# 05io.net
KiCad netlist of a schematic drawn in Altium Designer
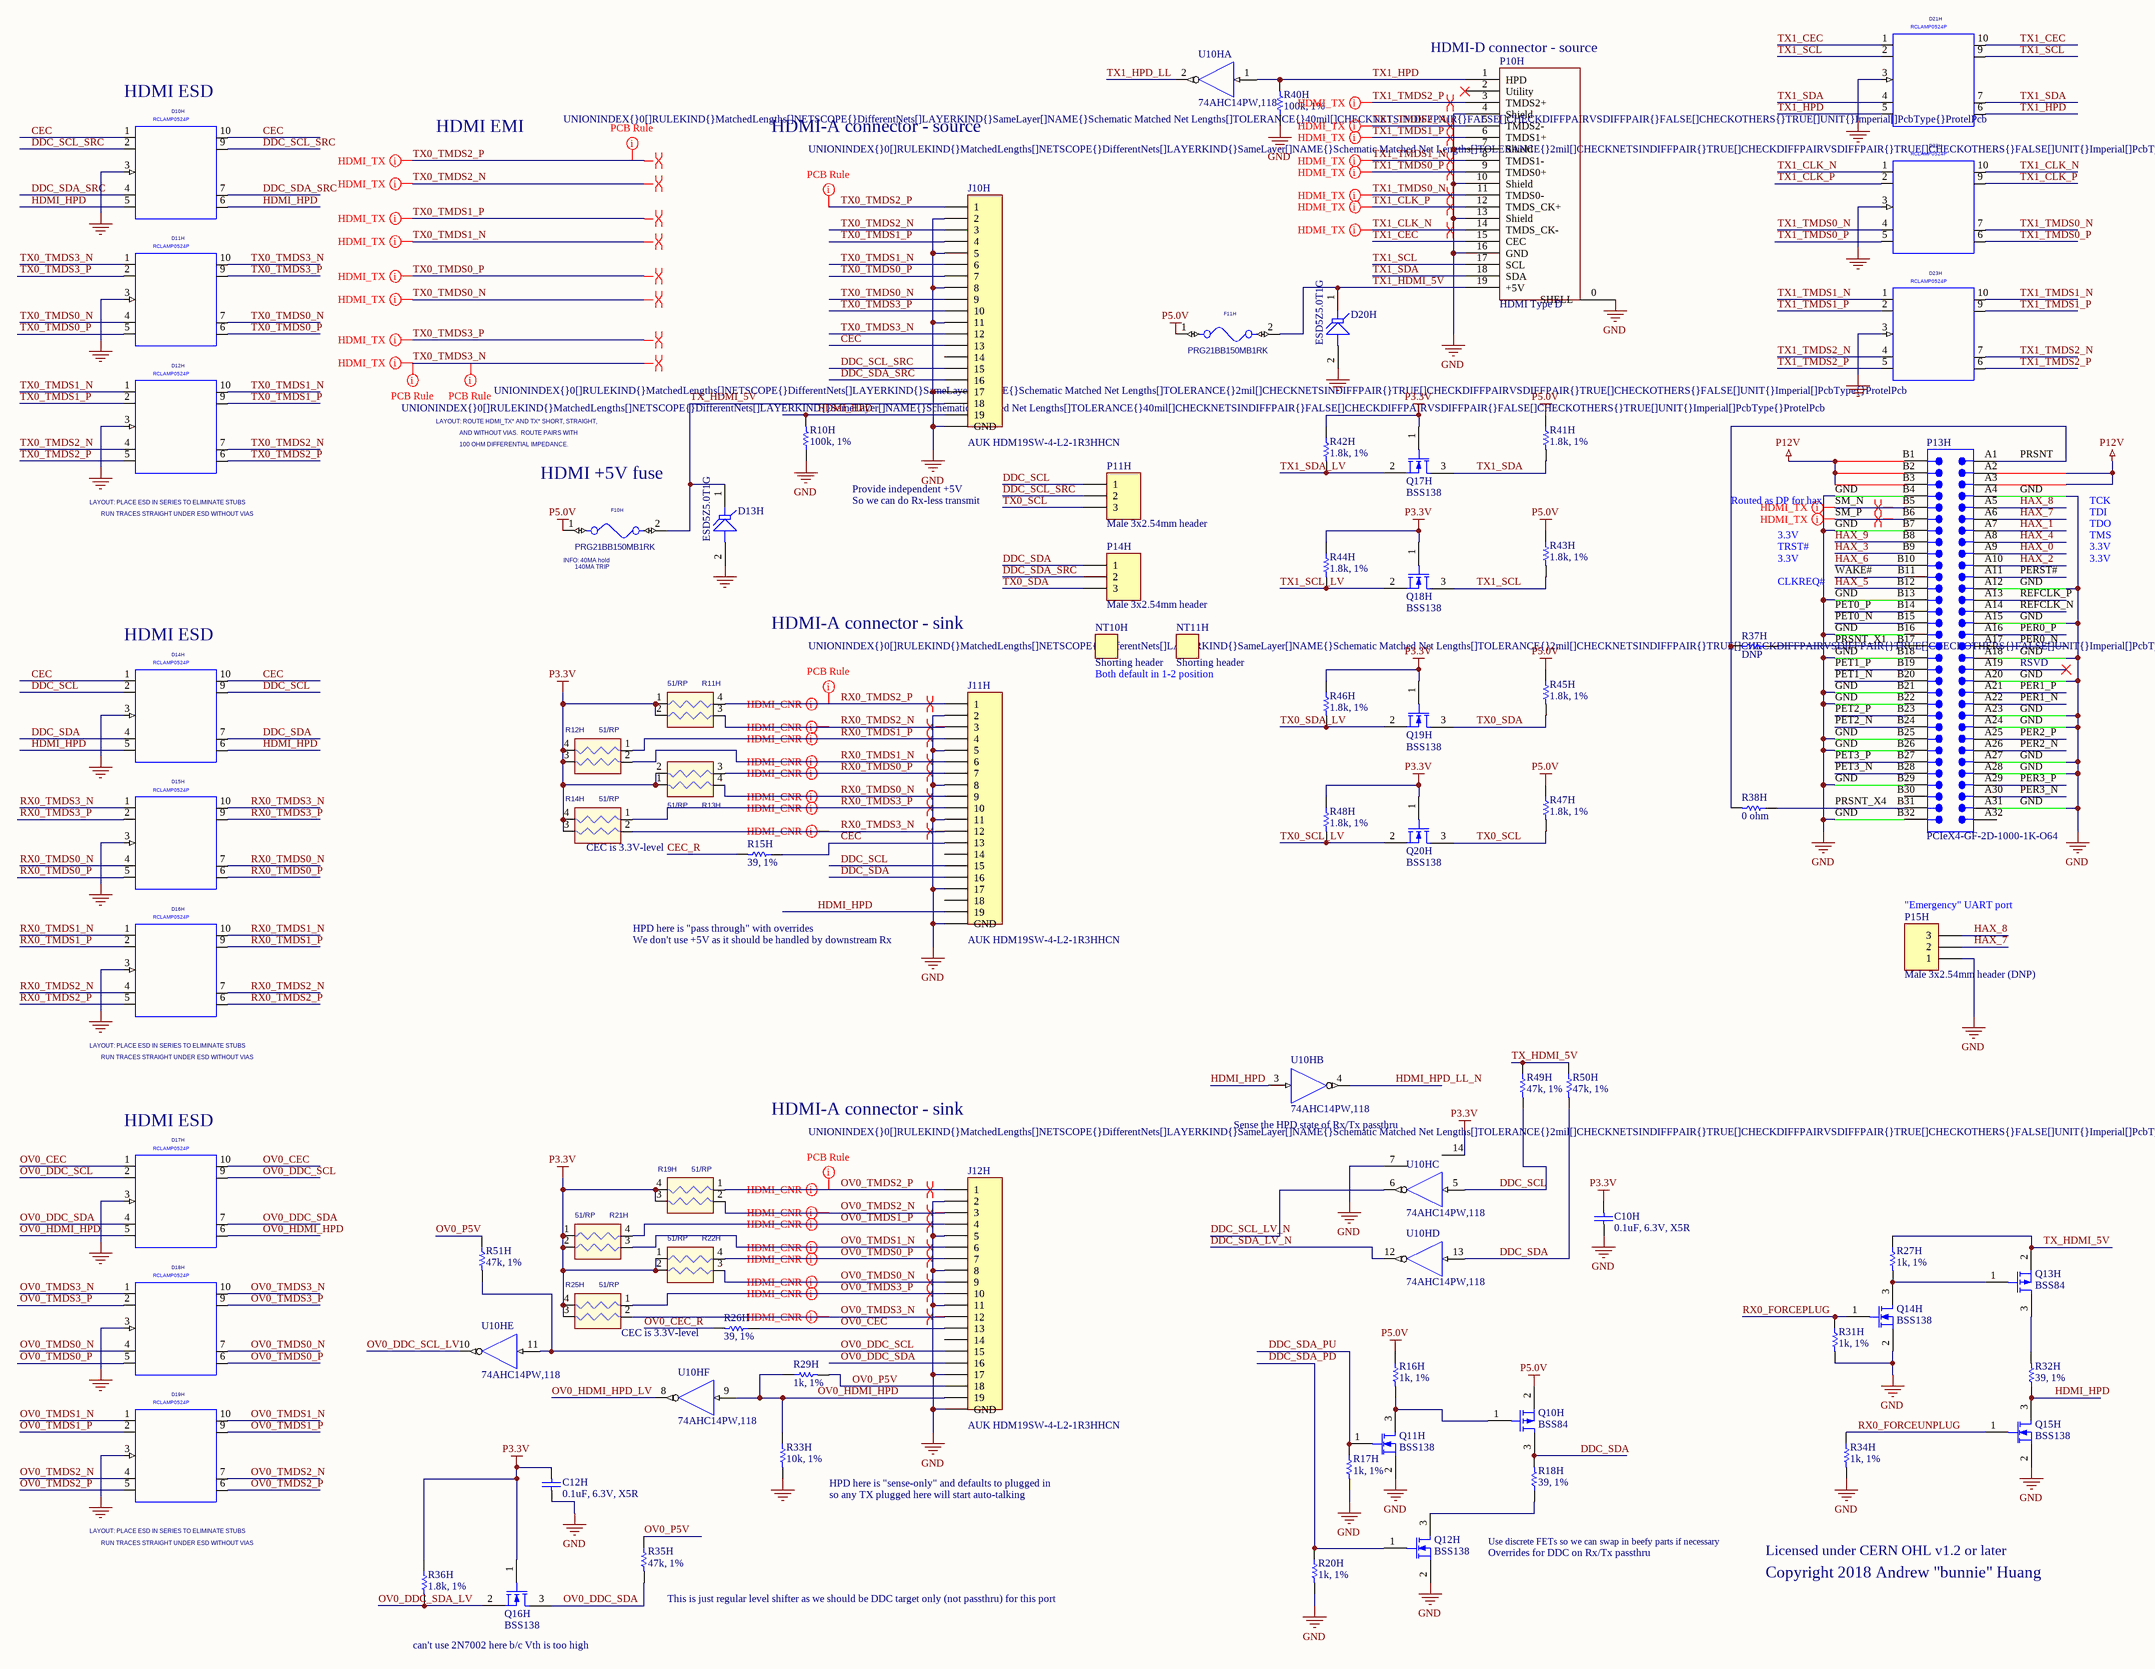
[diagram p0: 05io.SchDoc]

(export (version "E")
  (design (tool "Eeschema 10.0.6"))
  (components
    (comp (ref "C10H")
      (value "0.1uF, 6.3V, X5R")
      (footprint "CAPC0603X03L")
      (description "Capacitor (Semiconductor SIM Model)")
      (fields (field (name "MPN") "CL03A104KQ3NNNC"))
      (libsource (lib "Miscellaneous Devices") (part "Cap Semi"))
    )
    (comp (ref "C12H")
      (value "0.1uF, 6.3V, X5R")
      (footprint "CAPC0603X03L")
      (description "Capacitor (Semiconductor SIM Model)")
      (fields (field (name "MPN") "CL03A104KQ3NNNC"))
      (libsource (lib "Miscellaneous Devices") (part "Cap Semi"))
    )
    (comp (ref "D10H")
      (value "RCLAMP0524P")
      (fields (field (name "PART_NUMBER") "V00004-001") (field (name "MPN") "RCLAMP0524PATCT"))
      (libsource (lib "*") (part "RCLAMP0524P"))
    )
    (comp (ref "D11H")
      (value "RCLAMP0524P")
      (fields (field (name "PART_NUMBER") "V00004-001") (field (name "MPN") "RCLAMP0524PATCT"))
      (libsource (lib "*") (part "RCLAMP0524P"))
    )
    (comp (ref "D12H")
      (value "RCLAMP0524P")
      (fields (field (name "PART_NUMBER") "V00004-001") (field (name "MPN") "RCLAMP0524PATCT"))
      (libsource (lib "*") (part "RCLAMP0524P"))
    )
    (comp (ref "D13H")
      (value "ESD5Z5.0T1G")
      (footprint "SOD-523")
      (description "On Semi 5.0V standoff TVS diode")
      (fields (field (name "PUBLISHER") "Altium Limited"))
      (libsource (lib "Miscellaneous Devices") (part "Tranzorb"))
    )
    (comp (ref "D14H")
      (value "RCLAMP0524P")
      (fields (field (name "PART_NUMBER") "V00004-001") (field (name "MPN") "RCLAMP0524PATCT"))
      (libsource (lib "*") (part "RCLAMP0524P"))
    )
    (comp (ref "D15H")
      (value "RCLAMP0524P")
      (fields (field (name "PART_NUMBER") "V00004-001") (field (name "MPN") "RCLAMP0524PATCT"))
      (libsource (lib "*") (part "RCLAMP0524P"))
    )
    (comp (ref "D16H")
      (value "RCLAMP0524P")
      (fields (field (name "PART_NUMBER") "V00004-001") (field (name "MPN") "RCLAMP0524PATCT"))
      (libsource (lib "*") (part "RCLAMP0524P"))
    )
    (comp (ref "D17H")
      (value "RCLAMP0524P")
      (fields (field (name "PART_NUMBER") "V00004-001") (field (name "MPN") "RCLAMP0524PATCT"))
      (libsource (lib "*") (part "RCLAMP0524P"))
    )
    (comp (ref "D18H")
      (value "RCLAMP0524P")
      (fields (field (name "PART_NUMBER") "V00004-001") (field (name "MPN") "RCLAMP0524PATCT"))
      (libsource (lib "*") (part "RCLAMP0524P"))
    )
    (comp (ref "D19H")
      (value "RCLAMP0524P")
      (fields (field (name "PART_NUMBER") "V00004-001") (field (name "MPN") "RCLAMP0524PATCT"))
      (libsource (lib "*") (part "RCLAMP0524P"))
    )
    (comp (ref "D20H")
      (value "ESD5Z5.0T1G")
      (footprint "SOD-523")
      (description "On Semi 5.0V standoff TVS diode")
      (fields (field (name "PUBLISHER") "Altium Limited"))
      (libsource (lib "Miscellaneous Devices") (part "Tranzorb"))
    )
    (comp (ref "D21H")
      (value "RCLAMP0524P")
      (fields (field (name "PART_NUMBER") "V00004-001") (field (name "MPN") "RCLAMP0524PATCT"))
      (libsource (lib "*") (part "RCLAMP0524P"))
    )
    (comp (ref "D22H")
      (value "RCLAMP0524P")
      (fields (field (name "PART_NUMBER") "V00004-001") (field (name "MPN") "RCLAMP0524PATCT"))
      (libsource (lib "*") (part "RCLAMP0524P"))
    )
    (comp (ref "D23H")
      (value "RCLAMP0524P")
      (fields (field (name "PART_NUMBER") "V00004-001") (field (name "MPN") "RCLAMP0524PATCT"))
      (libsource (lib "*") (part "RCLAMP0524P"))
    )
    (comp (ref "F10H")
      (value "PRG21BB150MB1RK")
      (description "Murata 140mA fuse, 40mA hold")
      (fields (field (name "PART_NUMBER") "M00014-001") (field (name "MPN") "0ZCK0010FF2G"))
      (libsource (lib "*") (part "FUSE0805"))
    )
    (comp (ref "F11H")
      (value "PRG21BB150MB1RK")
      (description "Murata 140mA fuse, 40mA hold")
      (fields (field (name "PART_NUMBER") "M00014-001") (field (name "MPN") "0ZCK0010FF2G"))
      (libsource (lib "*") (part "FUSE0805"))
    )
    (comp (ref "J10H")
      (value "AUK HDM19SW-4-L2-1R3HHCN")
      (footprint "MOLEX_47151-0001")
      (description "Molex HDMI connector, Type A")
      (fields (field (name "MPN") "CHDMI-AFM2S-01-D") (field (name "PUBLISHER") "Altium Limited"))
      (libsource (lib "Miscellaneous Connectors") (part "Header 19"))
    )
    (comp (ref "J11H")
      (value "AUK HDM19SW-4-L2-1R3HHCN")
      (footprint "MOLEX_47151-0001")
      (description "Molex HDMI connector, Type A")
      (fields (field (name "MPN") "CHDMI-AFM2S-01-D") (field (name "PUBLISHER") "Altium Limited"))
      (libsource (lib "Miscellaneous Connectors") (part "Header 19"))
    )
    (comp (ref "J12H")
      (value "AUK HDM19SW-4-L2-1R3HHCN")
      (footprint "MOLEX_47151-0001")
      (description "Molex HDMI connector, Type A")
      (fields (field (name "MPN") "CHDMI-AFM2S-01-D") (field (name "PUBLISHER") "Altium Limited"))
      (libsource (lib "Miscellaneous Connectors") (part "Header 19"))
    )
    (comp (ref "NT10H")
      (value "Shorting header")
      (description "Placeholder for non-board BOM items")
      (fields (field (name "MPN") "NPB02SVAN-RC"))
      (libsource (lib "commonsch") (part "NOTE"))
    )
    (comp (ref "NT11H")
      (value "Shorting header")
      (description "Placeholder for non-board BOM items")
      (fields (field (name "MPN") "NPB02SVAN-RC"))
      (libsource (lib "commonsch") (part "NOTE"))
    )
    (comp (ref "P10H")
      (value "HDMI Type D")
      (footprint "MOLEX_0467651301")
      (description "HDMI Type D with through-hole mounts")
      (fields (field (name "MPN") "CHDMI-DFMS-01-D"))
      (libsource (lib "commonsch-new") (part "HDMI-TYPE-D"))
    )
    (comp (ref "P11H")
      (value "Male 3x2.54mm header")
      (footprint "HDR1X3")
      (description "Header, 3-Pin")
      (fields (field (name "MPN") "CP25411-03G-S116-X") (field (name "PUBLISHER") "Altium Limited"))
      (libsource (lib "Miscellaneous Connectors") (part "Header 3"))
    )
    (comp (ref "P13H")
      (value "PCIeX4-GF-2D-1000-1K-O64")
      (footprint "PCIeX4-GF-2D-1000-1K-O64")
      (description "Golden finger, PCIeX4, Dual, Opposite, Pitch 1mm, 64-Position")
      (fields (field (name "PUBLISHER") "Altium"))
      (libsource (lib "altium-import") (part "root_3_CMP-0001-00031-1_"))
    )
    (comp (ref "P14H")
      (value "Male 3x2.54mm header")
      (footprint "HDR1X3")
      (description "Header, 3-Pin")
      (fields (field (name "MPN") "CP25411-03G-S116-X") (field (name "PUBLISHER") "Altium Limited"))
      (libsource (lib "Miscellaneous Connectors") (part "Header 3"))
    )
    (comp (ref "P15H")
      (value "Male 3x2.54mm header (DNP)")
      (footprint "HDR1X3")
      (description "Header, 3-Pin")
      (fields (field (name "MPN") "DNP") (field (name "PUBLISHER") "Altium Limited"))
      (libsource (lib "") (part "Header 3_1"))
    )
    (comp (ref "Q10H")
      (value "BSS84")
      (footprint "SOT23-3N")
      (description "P-Channel MOSFET")
      (fields (field (name "PUBLISHER") "Altium Limited"))
      (libsource (lib "Miscellaneous Devices") (part "MOSFET-P"))
    )
    (comp (ref "Q11H")
      (value "BSS138")
      (footprint "SOT23-3N")
      (description "N-Channel MOSFET")
      (fields (field (name "MPN") "BSS138LT1G") (field (name "PUBLISHER") "Altium Limited"))
      (libsource (lib "Miscellaneous Devices") (part "MOSFET-N"))
    )
    (comp (ref "Q12H")
      (value "BSS138")
      (footprint "SOT23-3N")
      (description "N-Channel MOSFET")
      (fields (field (name "MPN") "BSS138LT1G") (field (name "PUBLISHER") "Altium Limited"))
      (libsource (lib "Miscellaneous Devices") (part "MOSFET-N"))
    )
    (comp (ref "Q13H")
      (value "BSS84")
      (footprint "SOT23-3N")
      (description "P-Channel MOSFET")
      (fields (field (name "PUBLISHER") "Altium Limited"))
      (libsource (lib "Miscellaneous Devices") (part "MOSFET-P"))
    )
    (comp (ref "Q14H")
      (value "BSS138")
      (footprint "SOT23-3N")
      (description "N-Channel MOSFET")
      (fields (field (name "MPN") "BSS138LT1G") (field (name "PUBLISHER") "Altium Limited"))
      (libsource (lib "Miscellaneous Devices") (part "MOSFET-N"))
    )
    (comp (ref "Q15H")
      (value "BSS138")
      (footprint "SOT23-3N")
      (description "N-Channel MOSFET")
      (fields (field (name "MPN") "BSS138LT1G") (field (name "PUBLISHER") "Altium Limited"))
      (libsource (lib "Miscellaneous Devices") (part "MOSFET-N"))
    )
    (comp (ref "Q16H")
      (value "BSS138")
      (footprint "SOT23-3N")
      (description "N-Channel MOSFET")
      (fields (field (name "MPN") "BSS138LT1G") (field (name "PUBLISHER") "Altium Limited"))
      (libsource (lib "Miscellaneous Devices") (part "MOSFET-N"))
    )
    (comp (ref "Q17H")
      (value "BSS138")
      (footprint "SOT23-3N")
      (description "N-Channel MOSFET")
      (fields (field (name "MPN") "BSS138LT1G") (field (name "PUBLISHER") "Altium Limited"))
      (libsource (lib "Miscellaneous Devices") (part "MOSFET-N"))
    )
    (comp (ref "Q18H")
      (value "BSS138")
      (footprint "SOT23-3N")
      (description "N-Channel MOSFET")
      (fields (field (name "MPN") "BSS138LT1G") (field (name "PUBLISHER") "Altium Limited"))
      (libsource (lib "Miscellaneous Devices") (part "MOSFET-N"))
    )
    (comp (ref "Q19H")
      (value "BSS138")
      (footprint "SOT23-3N")
      (description "N-Channel MOSFET")
      (fields (field (name "MPN") "BSS138LT1G") (field (name "PUBLISHER") "Altium Limited"))
      (libsource (lib "Miscellaneous Devices") (part "MOSFET-N"))
    )
    (comp (ref "Q20H")
      (value "BSS138")
      (footprint "SOT23-3N")
      (description "N-Channel MOSFET")
      (fields (field (name "MPN") "BSS138LT1G") (field (name "PUBLISHER") "Altium Limited"))
      (libsource (lib "Miscellaneous Devices") (part "MOSFET-N"))
    )
    (comp (ref "R10H")
      (value "100k, 1%")
      (footprint "RESC1005N")
      (description "Resistor")
      (fields (field (name "MPN") "ANY"))
      (libsource (lib "Miscellaneous Devices") (part "Res1"))
    )
    (comp (ref "R11H")
      (value "51/RP")
      (fields (field (name "MPN") "RP102PJ510CS") (field (name "MFG") "SAMSUNG"))
      (libsource (lib "*") (part "RPACK2"))
    )
    (comp (ref "R12H")
      (value "51/RP")
      (fields (field (name "MPN") "RP102PJ510CS") (field (name "MFG") "SAMSUNG"))
      (libsource (lib "") (part "RPACK2_1"))
    )
    (comp (ref "R13H")
      (value "51/RP")
      (fields (field (name "MPN") "RP102PJ510CS") (field (name "MFG") "SAMSUNG"))
      (libsource (lib "") (part "RPACK2_2"))
    )
    (comp (ref "R14H")
      (value "51/RP")
      (fields (field (name "MPN") "RP102PJ510CS") (field (name "MFG") "SAMSUNG"))
      (libsource (lib "") (part "RPACK2_1"))
    )
    (comp (ref "R15H")
      (value "39, 1%")
      (footprint "RESC1005N")
      (description "Resistor")
      (fields (field (name "MPN") "ANY"))
      (libsource (lib "Miscellaneous Devices") (part "Res1"))
    )
    (comp (ref "R16H")
      (value "1k, 1%")
      (footprint "RESC1005N")
      (description "Resistor")
      (fields (field (name "MPN") "RS02U102FT"))
      (libsource (lib "Miscellaneous Devices") (part "Res1"))
    )
    (comp (ref "R17H")
      (value "1k, 1%")
      (footprint "RESC1005N")
      (description "Resistor")
      (fields (field (name "MPN") "RS02U102FT"))
      (libsource (lib "Miscellaneous Devices") (part "Res1"))
    )
    (comp (ref "R18H")
      (value "39, 1%")
      (footprint "RESC1005N")
      (description "Resistor")
      (fields (field (name "MPN") "ANY"))
      (libsource (lib "Miscellaneous Devices") (part "Res1"))
    )
    (comp (ref "R19H")
      (value "51/RP")
      (fields (field (name "MPN") "RP102PJ510CS") (field (name "MFG") "SAMSUNG"))
      (libsource (lib "") (part "RPACK2_1"))
    )
    (comp (ref "R20H")
      (value "1k, 1%")
      (footprint "RESC1005N")
      (description "Resistor")
      (fields (field (name "MPN") "RS02U102FT"))
      (libsource (lib "Miscellaneous Devices") (part "Res1"))
    )
    (comp (ref "R21H")
      (value "51/RP")
      (fields (field (name "MPN") "RP102PJ510CS") (field (name "MFG") "SAMSUNG"))
      (libsource (lib "*") (part "RPACK2"))
    )
    (comp (ref "R22H")
      (value "51/RP")
      (fields (field (name "MPN") "RP102PJ510CS") (field (name "MFG") "SAMSUNG"))
      (libsource (lib "*") (part "RPACK2"))
    )
    (comp (ref "R25H")
      (value "51/RP")
      (fields (field (name "MPN") "RP102PJ510CS") (field (name "MFG") "SAMSUNG"))
      (libsource (lib "") (part "RPACK2_1"))
    )
    (comp (ref "R26H")
      (value "39, 1%")
      (footprint "RESC1005N")
      (description "Resistor")
      (fields (field (name "MPN") "ANY"))
      (libsource (lib "Miscellaneous Devices") (part "Res1"))
    )
    (comp (ref "R27H")
      (value "1k, 1%")
      (footprint "RESC1005N")
      (description "Resistor")
      (fields (field (name "MPN") "RS02U102FT"))
      (libsource (lib "Miscellaneous Devices") (part "Res1"))
    )
    (comp (ref "R29H")
      (value "1k, 1%")
      (footprint "RESC1005N")
      (description "Resistor")
      (fields (field (name "MPN") "RS02U102FT"))
      (libsource (lib "Miscellaneous Devices") (part "Res1"))
    )
    (comp (ref "R31H")
      (value "1k, 1%")
      (footprint "RESC1005N")
      (description "Resistor")
      (fields (field (name "MPN") "RS02U102FT"))
      (libsource (lib "Miscellaneous Devices") (part "Res1"))
    )
    (comp (ref "R32H")
      (value "39, 1%")
      (footprint "RESC1005N")
      (description "Resistor")
      (fields (field (name "MPN") "ANY"))
      (libsource (lib "Miscellaneous Devices") (part "Res1"))
    )
    (comp (ref "R33H")
      (value "10k, 1%")
      (footprint "RESC1005N")
      (description "Resistor")
      (fields (field (name "MPN") "RS02U103FT"))
      (libsource (lib "Miscellaneous Devices") (part "Res1"))
    )
    (comp (ref "R34H")
      (value "1k, 1%")
      (footprint "RESC1005N")
      (description "Resistor")
      (fields (field (name "MPN") "RS02U102FT"))
      (libsource (lib "Miscellaneous Devices") (part "Res1"))
    )
    (comp (ref "R35H")
      (value "47k, 1%")
      (footprint "RESC1005N")
      (description "Resistor")
      (fields (field (name "MPN") "RS02U473FT") (field (name "PUBLISHER") "Altium Limited"))
      (libsource (lib "Miscellaneous Devices") (part "Res1"))
    )
    (comp (ref "R36H")
      (value "1.8k, 1%")
      (footprint "RESC1005N")
      (description "Resistor")
      (fields (field (name "MPN") "RS02U182FT") (field (name "PUBLISHER") "Altium Limited"))
      (libsource (lib "Miscellaneous Devices") (part "Res1"))
    )
    (comp (ref "R37H")
      (value "DNP")
      (footprint "RESC1608N")
      (description "Resistor")
      (fields (field (name "MPN") "ANY"))
      (libsource (lib "Miscellaneous Devices") (part "Res1"))
    )
    (comp (ref "R38H")
      (value "0 ohm")
      (footprint "RESC1608N")
      (description "Resistor")
      (fields (field (name "MPN") "ANY"))
      (libsource (lib "Miscellaneous Devices") (part "Res1"))
    )
    (comp (ref "R40H")
      (value "100k, 1%")
      (footprint "RESC1005N")
      (description "Resistor")
      (fields (field (name "MPN") "ANY"))
      (libsource (lib "Miscellaneous Devices") (part "Res1"))
    )
    (comp (ref "R41H")
      (value "1.8k, 1%")
      (footprint "RESC1005N")
      (description "Resistor")
      (fields (field (name "MPN") "RS02U182FT") (field (name "PUBLISHER") "Altium Limited"))
      (libsource (lib "Miscellaneous Devices") (part "Res1"))
    )
    (comp (ref "R42H")
      (value "1.8k, 1%")
      (footprint "RESC1005N")
      (description "Resistor")
      (fields (field (name "MPN") "RS02U182FT") (field (name "PUBLISHER") "Altium Limited"))
      (libsource (lib "Miscellaneous Devices") (part "Res1"))
    )
    (comp (ref "R43H")
      (value "1.8k, 1%")
      (footprint "RESC1005N")
      (description "Resistor")
      (fields (field (name "MPN") "RS02U182FT") (field (name "PUBLISHER") "Altium Limited"))
      (libsource (lib "Miscellaneous Devices") (part "Res1"))
    )
    (comp (ref "R44H")
      (value "1.8k, 1%")
      (footprint "RESC1005N")
      (description "Resistor")
      (fields (field (name "MPN") "RS02U182FT") (field (name "PUBLISHER") "Altium Limited"))
      (libsource (lib "Miscellaneous Devices") (part "Res1"))
    )
    (comp (ref "R45H")
      (value "1.8k, 1%")
      (footprint "RESC1005N")
      (description "Resistor")
      (fields (field (name "MPN") "RS02U182FT") (field (name "PUBLISHER") "Altium Limited"))
      (libsource (lib "Miscellaneous Devices") (part "Res1"))
    )
    (comp (ref "R46H")
      (value "1.8k, 1%")
      (footprint "RESC1005N")
      (description "Resistor")
      (fields (field (name "MPN") "RS02U182FT") (field (name "PUBLISHER") "Altium Limited"))
      (libsource (lib "Miscellaneous Devices") (part "Res1"))
    )
    (comp (ref "R47H")
      (value "1.8k, 1%")
      (footprint "RESC1005N")
      (description "Resistor")
      (fields (field (name "MPN") "RS02U182FT") (field (name "PUBLISHER") "Altium Limited"))
      (libsource (lib "Miscellaneous Devices") (part "Res1"))
    )
    (comp (ref "R48H")
      (value "1.8k, 1%")
      (footprint "RESC1005N")
      (description "Resistor")
      (fields (field (name "MPN") "RS02U182FT") (field (name "PUBLISHER") "Altium Limited"))
      (libsource (lib "Miscellaneous Devices") (part "Res1"))
    )
    (comp (ref "R49H")
      (value "47k, 1%")
      (footprint "RESC1005N")
      (description "Resistor")
      (fields (field (name "MPN") "RS02U473FT") (field (name "PUBLISHER") "Altium Limited"))
      (libsource (lib "Miscellaneous Devices") (part "Res1"))
    )
    (comp (ref "R50H")
      (value "47k, 1%")
      (footprint "RESC1005N")
      (description "Resistor")
      (fields (field (name "MPN") "RS02U473FT") (field (name "PUBLISHER") "Altium Limited"))
      (libsource (lib "Miscellaneous Devices") (part "Res1"))
    )
    (comp (ref "R51H")
      (value "47k, 1%")
      (footprint "RESC1005N")
      (description "Resistor")
      (fields (field (name "MPN") "RS02U473FT") (field (name "PUBLISHER") "Altium Limited"))
      (libsource (lib "Miscellaneous Devices") (part "Res1"))
    )
    (comp (ref "U10H")
      (value "74AHC14PW,118")
      (footprint "TSOP65P640-14AN")
      (description "Hex Inverter, 14-Pin SOIC, Commercial Grade")
      (fields (field (name "PUBLISHER") "Altium Limited"))
      (libsource (lib "FSC Logic Gate") (part "74AC04SC"))
    )
  )
  (nets
    (net (code "1") (name "/CEC") (class "Default")
      (node (ref "D10H") (pin "1") (pinfunction "IO1A_1") (pintype "bidirectional"))
      (node (ref "D10H") (pin "10") (pinfunction "IO1B_10") (pintype "bidirectional"))
      (node (ref "D14H") (pin "1") (pinfunction "IO1A_1") (pintype "bidirectional"))
      (node (ref "D14H") (pin "10") (pinfunction "IO1B_10") (pintype "bidirectional"))
      (node (ref "J10H") (pin "13") (pinfunction "13_13") (pintype "passive"))
      (node (ref "J11H") (pin "13") (pinfunction "13_13") (pintype "passive"))
      (node (ref "R15H") (pin "1") (pinfunction "1_1") (pintype "passive"))
    )
    (net (code "2") (name "/CEC_R") (class "Default")
      (node (ref "R15H") (pin "2") (pinfunction "2_2") (pintype "passive"))
    )
    (net (code "3") (name "/DDC_SCL") (class "Default")
      (node (ref "D14H") (pin "2") (pinfunction "IO2A_2") (pintype "bidirectional"))
      (node (ref "D14H") (pin "9") (pinfunction "IO2B_9") (pintype "bidirectional"))
      (node (ref "J11H") (pin "15") (pinfunction "15_15") (pintype "passive"))
      (node (ref "P11H") (pin "1") (pinfunction "1_1") (pintype "passive"))
      (node (ref "R49H") (pin "2") (pinfunction "2_2") (pintype "passive"))
      (node (ref "U10H") (pin "5") (pinfunction "A_5") (pintype "input"))
    )
    (net (code "4") (name "/DDC_SCL_LV_N") (class "Default")
      (node (ref "U10H") (pin "6") (pinfunction "~{O}_6") (pintype "output"))
    )
    (net (code "5") (name "/DDC_SCL_SRC") (class "Default")
      (node (ref "D10H") (pin "2") (pinfunction "IO2A_2") (pintype "bidirectional"))
      (node (ref "D10H") (pin "9") (pinfunction "IO2B_9") (pintype "bidirectional"))
      (node (ref "J10H") (pin "15") (pinfunction "15_15") (pintype "passive"))
      (node (ref "P11H") (pin "2") (pinfunction "2_2") (pintype "passive"))
    )
    (net (code "6") (name "/DDC_SDA") (class "Default")
      (node (ref "D14H") (pin "4") (pinfunction "IO3A_4") (pintype "bidirectional"))
      (node (ref "D14H") (pin "7") (pinfunction "IO3B_7") (pintype "bidirectional"))
      (node (ref "J11H") (pin "16") (pinfunction "16_16") (pintype "passive"))
      (node (ref "P14H") (pin "1") (pinfunction "1_1") (pintype "passive"))
      (node (ref "Q10H") (pin "3") (pinfunction "D_3") (pintype "passive"))
      (node (ref "R18H") (pin "2") (pinfunction "2_2") (pintype "passive"))
      (node (ref "R50H") (pin "2") (pinfunction "2_2") (pintype "passive"))
      (node (ref "U10H") (pin "13") (pinfunction "A_13") (pintype "input"))
    )
    (net (code "7") (name "/DDC_SDA_LV_N") (class "Default")
      (node (ref "U10H") (pin "12") (pinfunction "~{O}_12") (pintype "output"))
    )
    (net (code "8") (name "/DDC_SDA_PD") (class "Default")
      (node (ref "Q12H") (pin "1") (pinfunction "G_1") (pintype "passive"))
      (node (ref "R20H") (pin "1") (pinfunction "1_1") (pintype "passive"))
    )
    (net (code "9") (name "/DDC_SDA_PU") (class "Default")
      (node (ref "Q11H") (pin "1") (pinfunction "G_1") (pintype "passive"))
      (node (ref "R17H") (pin "1") (pinfunction "1_1") (pintype "passive"))
    )
    (net (code "10") (name "/DDC_SDA_SRC") (class "Default")
      (node (ref "D10H") (pin "4") (pinfunction "IO3A_4") (pintype "bidirectional"))
      (node (ref "D10H") (pin "7") (pinfunction "IO3B_7") (pintype "bidirectional"))
      (node (ref "J10H") (pin "16") (pinfunction "16_16") (pintype "passive"))
      (node (ref "P14H") (pin "2") (pinfunction "2_2") (pintype "passive"))
    )
    (net (code "11") (name "/HAX_0") (class "Default")
      (node (ref "P13H") (pin "A9") (pinfunction "A9_A9") (pintype "passive"))
    )
    (net (code "12") (name "/HAX_1") (class "Default")
      (node (ref "P13H") (pin "A7") (pinfunction "A7_A7") (pintype "passive"))
    )
    (net (code "13") (name "/HAX_2") (class "Default")
      (node (ref "P13H") (pin "A10") (pinfunction "A10_A10") (pintype "passive"))
    )
    (net (code "14") (name "/HAX_3") (class "Default")
      (node (ref "P13H") (pin "B9") (pinfunction "B9_B9") (pintype "passive"))
    )
    (net (code "15") (name "/HAX_4") (class "Default")
      (node (ref "P13H") (pin "A8") (pinfunction "A8_A8") (pintype "passive"))
    )
    (net (code "16") (name "/HAX_5") (class "Default")
      (node (ref "P13H") (pin "B12") (pinfunction "B12_B12") (pintype "passive"))
    )
    (net (code "17") (name "/HAX_6") (class "Default")
      (node (ref "P13H") (pin "B10") (pinfunction "B10_B10") (pintype "passive"))
    )
    (net (code "18") (name "/HAX_7") (class "Default")
      (node (ref "P13H") (pin "A6") (pinfunction "A6_A6") (pintype "passive"))
      (node (ref "P15H") (pin "2") (pinfunction "2_2") (pintype "passive"))
    )
    (net (code "19") (name "/HAX_8") (class "Default")
      (node (ref "P13H") (pin "A5") (pinfunction "A5_A5") (pintype "passive"))
      (node (ref "P15H") (pin "3") (pinfunction "3_3") (pintype "passive"))
    )
    (net (code "20") (name "/HAX_9") (class "Default")
      (node (ref "P13H") (pin "B8") (pinfunction "B8_B8") (pintype "passive"))
    )
    (net (code "21") (name "/HDMI_HPD") (class "Default")
      (node (ref "D10H") (pin "5") (pinfunction "IO4A_5") (pintype "bidirectional"))
      (node (ref "D10H") (pin "6") (pinfunction "IO4B_6") (pintype "bidirectional"))
      (node (ref "D14H") (pin "5") (pinfunction "IO4A_5") (pintype "bidirectional"))
      (node (ref "D14H") (pin "6") (pinfunction "IO4B_6") (pintype "bidirectional"))
      (node (ref "J10H") (pin "19") (pinfunction "19_19") (pintype "passive"))
      (node (ref "J11H") (pin "19") (pinfunction "19_19") (pintype "passive"))
      (node (ref "Q15H") (pin "3") (pinfunction "D_3") (pintype "passive"))
      (node (ref "R10H") (pin "2") (pinfunction "2_2") (pintype "passive"))
      (node (ref "R32H") (pin "1") (pinfunction "1_1") (pintype "passive"))
      (node (ref "U10H") (pin "3") (pinfunction "A_3") (pintype "input"))
    )
    (net (code "22") (name "/HDMI_HPD_LL_N") (class "Default")
      (node (ref "U10H") (pin "4") (pinfunction "~{O}_4") (pintype "output"))
    )
    (net (code "23") (name "/OV0_CEC") (class "Default")
      (node (ref "D17H") (pin "1") (pinfunction "IO1A_1") (pintype "bidirectional"))
      (node (ref "D17H") (pin "10") (pinfunction "IO1B_10") (pintype "bidirectional"))
      (node (ref "J12H") (pin "13") (pinfunction "13_13") (pintype "passive"))
      (node (ref "R26H") (pin "1") (pinfunction "1_1") (pintype "passive"))
    )
    (net (code "24") (name "/OV0_CEC_R") (class "Default")
      (node (ref "R26H") (pin "2") (pinfunction "2_2") (pintype "passive"))
    )
    (net (code "25") (name "/OV0_DDC_SCL") (class "Default")
      (node (ref "D17H") (pin "2") (pinfunction "IO2A_2") (pintype "bidirectional"))
      (node (ref "D17H") (pin "9") (pinfunction "IO2B_9") (pintype "bidirectional"))
      (node (ref "J12H") (pin "15") (pinfunction "15_15") (pintype "passive"))
      (node (ref "R51H") (pin "2") (pinfunction "2_2") (pintype "passive"))
      (node (ref "U10H") (pin "11") (pinfunction "A_11") (pintype "input"))
    )
    (net (code "26") (name "/OV0_DDC_SCL_LV") (class "Default")
      (node (ref "U10H") (pin "10") (pinfunction "~{O}_10") (pintype "output"))
    )
    (net (code "27") (name "/OV0_DDC_SDA") (class "Default")
      (node (ref "D17H") (pin "4") (pinfunction "IO3A_4") (pintype "bidirectional"))
      (node (ref "D17H") (pin "7") (pinfunction "IO3B_7") (pintype "bidirectional"))
      (node (ref "J12H") (pin "16") (pinfunction "16_16") (pintype "passive"))
      (node (ref "Q16H") (pin "3") (pinfunction "D_3") (pintype "passive"))
      (node (ref "R35H") (pin "2") (pinfunction "2_2") (pintype "passive"))
    )
    (net (code "28") (name "/OV0_DDC_SDA_LV") (class "Default")
      (node (ref "Q16H") (pin "2") (pinfunction "S_2") (pintype "passive"))
      (node (ref "R36H") (pin "2") (pinfunction "2_2") (pintype "passive"))
    )
    (net (code "29") (name "/OV0_HDMI_HPD") (class "Default")
      (node (ref "D17H") (pin "5") (pinfunction "IO4A_5") (pintype "bidirectional"))
      (node (ref "D17H") (pin "6") (pinfunction "IO4B_6") (pintype "bidirectional"))
      (node (ref "J12H") (pin "19") (pinfunction "19_19") (pintype "passive"))
      (node (ref "R29H") (pin "1") (pinfunction "1_1") (pintype "passive"))
      (node (ref "R33H") (pin "1") (pinfunction "1_1") (pintype "passive"))
      (node (ref "U10H") (pin "9") (pinfunction "A_9") (pintype "input"))
    )
    (net (code "30") (name "/OV0_HDMI_HPD_LV") (class "Default")
      (node (ref "U10H") (pin "8") (pinfunction "~{O}_8") (pintype "output"))
    )
    (net (code "31") (name "/OV0_P5V") (class "Default")
      (node (ref "J12H") (pin "18") (pinfunction "18_18") (pintype "passive"))
      (node (ref "R29H") (pin "2") (pinfunction "2_2") (pintype "passive"))
      (node (ref "R35H") (pin "1") (pinfunction "1_1") (pintype "passive"))
      (node (ref "R51H") (pin "1") (pinfunction "1_1") (pintype "passive"))
    )
    (net (code "32") (name "/OV0_TMDS0_N") (class "Default")
      (node (ref "D18H") (pin "4") (pinfunction "IO3A_4") (pintype "bidirectional"))
      (node (ref "D18H") (pin "7") (pinfunction "IO3B_7") (pintype "bidirectional"))
      (node (ref "J12H") (pin "9") (pinfunction "9_9") (pintype "passive"))
      (node (ref "R22H") (pin "3") (pinfunction "R22_3") (pintype "passive"))
    )
    (net (code "33") (name "/OV0_TMDS0_P") (class "Default")
      (node (ref "D18H") (pin "5") (pinfunction "IO4A_5") (pintype "bidirectional"))
      (node (ref "D18H") (pin "6") (pinfunction "IO4B_6") (pintype "bidirectional"))
      (node (ref "J12H") (pin "7") (pinfunction "7_7") (pintype "passive"))
      (node (ref "R22H") (pin "4") (pinfunction "R12_4") (pintype "passive"))
    )
    (net (code "34") (name "/OV0_TMDS1_N") (class "Default")
      (node (ref "D19H") (pin "1") (pinfunction "IO1A_1") (pintype "bidirectional"))
      (node (ref "D19H") (pin "10") (pinfunction "IO1B_10") (pintype "bidirectional"))
      (node (ref "J12H") (pin "6") (pinfunction "6_6") (pintype "passive"))
      (node (ref "R21H") (pin "3") (pinfunction "R22_3") (pintype "passive"))
    )
    (net (code "35") (name "/OV0_TMDS1_P") (class "Default")
      (node (ref "D19H") (pin "2") (pinfunction "IO2A_2") (pintype "bidirectional"))
      (node (ref "D19H") (pin "9") (pinfunction "IO2B_9") (pintype "bidirectional"))
      (node (ref "J12H") (pin "4") (pinfunction "4_4") (pintype "passive"))
      (node (ref "R21H") (pin "4") (pinfunction "R12_4") (pintype "passive"))
    )
    (net (code "36") (name "/OV0_TMDS2_N") (class "Default")
      (node (ref "D19H") (pin "4") (pinfunction "IO3A_4") (pintype "bidirectional"))
      (node (ref "D19H") (pin "7") (pinfunction "IO3B_7") (pintype "bidirectional"))
      (node (ref "J12H") (pin "3") (pinfunction "3_3") (pintype "passive"))
      (node (ref "R19H") (pin "2") (pinfunction "R2_2") (pintype "passive"))
    )
    (net (code "37") (name "/OV0_TMDS2_P") (class "Default")
      (node (ref "D19H") (pin "5") (pinfunction "IO4A_5") (pintype "bidirectional"))
      (node (ref "D19H") (pin "6") (pinfunction "IO4B_6") (pintype "bidirectional"))
      (node (ref "J12H") (pin "1") (pinfunction "1_1") (pintype "passive"))
      (node (ref "R19H") (pin "1") (pinfunction "R1_1") (pintype "passive"))
    )
    (net (code "38") (name "/OV0_TMDS3_N") (class "Default")
      (node (ref "D18H") (pin "1") (pinfunction "IO1A_1") (pintype "bidirectional"))
      (node (ref "D18H") (pin "10") (pinfunction "IO1B_10") (pintype "bidirectional"))
      (node (ref "J12H") (pin "12") (pinfunction "12_12") (pintype "passive"))
      (node (ref "R25H") (pin "2") (pinfunction "R2_2") (pintype "passive"))
    )
    (net (code "39") (name "/OV0_TMDS3_P") (class "Default")
      (node (ref "D18H") (pin "2") (pinfunction "IO2A_2") (pintype "bidirectional"))
      (node (ref "D18H") (pin "9") (pinfunction "IO2B_9") (pintype "bidirectional"))
      (node (ref "J12H") (pin "10") (pinfunction "10_10") (pintype "passive"))
      (node (ref "R25H") (pin "1") (pinfunction "R1_1") (pintype "passive"))
    )
    (net (code "40") (name "/PER0_N") (class "Default")
      (node (ref "P13H") (pin "A17") (pinfunction "A17_A17") (pintype "passive"))
    )
    (net (code "41") (name "/PER0_P") (class "Default")
      (node (ref "P13H") (pin "A16") (pinfunction "A16_A16") (pintype "passive"))
    )
    (net (code "42") (name "/PER1_N") (class "Default")
      (node (ref "P13H") (pin "A22") (pinfunction "A22_A22") (pintype "passive"))
    )
    (net (code "43") (name "/PER1_P") (class "Default")
      (node (ref "P13H") (pin "A21") (pinfunction "A21_A21") (pintype "passive"))
    )
    (net (code "44") (name "/PER2_N") (class "Default")
      (node (ref "P13H") (pin "A26") (pinfunction "A26_A26") (pintype "passive"))
    )
    (net (code "45") (name "/PER2_P") (class "Default")
      (node (ref "P13H") (pin "A25") (pinfunction "A25_A25") (pintype "passive"))
    )
    (net (code "46") (name "/PER3_N") (class "Default")
      (node (ref "P13H") (pin "A30") (pinfunction "A30_A30") (pintype "passive"))
    )
    (net (code "47") (name "/PER3_P") (class "Default")
      (node (ref "P13H") (pin "A29") (pinfunction "A29_A29") (pintype "passive"))
    )
    (net (code "48") (name "/PERST#") (class "Default")
      (node (ref "P13H") (pin "A11") (pinfunction "A11_A11") (pintype "passive"))
    )
    (net (code "49") (name "/PET0_N") (class "Default")
      (node (ref "P13H") (pin "B15") (pinfunction "B15_B15") (pintype "passive"))
    )
    (net (code "50") (name "/PET0_P") (class "Default")
      (node (ref "P13H") (pin "B14") (pinfunction "B14_B14") (pintype "passive"))
    )
    (net (code "51") (name "/PET1_N") (class "Default")
      (node (ref "P13H") (pin "B20") (pinfunction "B20_B20") (pintype "passive"))
    )
    (net (code "52") (name "/PET1_P") (class "Default")
      (node (ref "P13H") (pin "B19") (pinfunction "B19_B19") (pintype "passive"))
    )
    (net (code "53") (name "/PET2_N") (class "Default")
      (node (ref "P13H") (pin "B24") (pinfunction "B24_B24") (pintype "passive"))
    )
    (net (code "54") (name "/PET2_P") (class "Default")
      (node (ref "P13H") (pin "B23") (pinfunction "B23_B23") (pintype "passive"))
    )
    (net (code "55") (name "/PET3_N") (class "Default")
      (node (ref "P13H") (pin "B28") (pinfunction "B28_B28") (pintype "passive"))
    )
    (net (code "56") (name "/PET3_P") (class "Default")
      (node (ref "P13H") (pin "B27") (pinfunction "B27_B27") (pintype "passive"))
    )
    (net (code "57") (name "/PRSNT") (class "Default")
      (node (ref "P13H") (pin "A1") (pinfunction "A1_A1") (pintype "passive"))
      (node (ref "R37H") (pin "2") (pinfunction "2_2") (pintype "passive"))
      (node (ref "R38H") (pin "2") (pinfunction "2_2") (pintype "passive"))
    )
    (net (code "58") (name "/PRSNT_X1") (class "Default")
      (node (ref "P13H") (pin "B17") (pinfunction "B17_B17") (pintype "passive"))
      (node (ref "R37H") (pin "1") (pinfunction "1_1") (pintype "passive"))
    )
    (net (code "59") (name "/PRSNT_X4") (class "Default")
      (node (ref "P13H") (pin "B31") (pinfunction "B31_B31") (pintype "passive"))
      (node (ref "R38H") (pin "1") (pinfunction "1_1") (pintype "passive"))
    )
    (net (code "60") (name "/REFCLK_N") (class "Default")
      (node (ref "P13H") (pin "A14") (pinfunction "A14_A14") (pintype "passive"))
    )
    (net (code "61") (name "/REFCLK_P") (class "Default")
      (node (ref "P13H") (pin "A13") (pinfunction "A13_A13") (pintype "passive"))
    )
    (net (code "62") (name "/RX0_FORCEPLUG") (class "Default")
      (node (ref "Q14H") (pin "1") (pinfunction "G_1") (pintype "passive"))
      (node (ref "R31H") (pin "1") (pinfunction "1_1") (pintype "passive"))
    )
    (net (code "63") (name "/RX0_FORCEUNPLUG") (class "Default")
      (node (ref "Q15H") (pin "1") (pinfunction "G_1") (pintype "passive"))
      (node (ref "R34H") (pin "1") (pinfunction "1_1") (pintype "passive"))
    )
    (net (code "64") (name "/RX0_TMDS0_N") (class "Default")
      (node (ref "D15H") (pin "4") (pinfunction "IO3A_4") (pintype "bidirectional"))
      (node (ref "D15H") (pin "7") (pinfunction "IO3B_7") (pintype "bidirectional"))
      (node (ref "J11H") (pin "9") (pinfunction "9_9") (pintype "passive"))
      (node (ref "R13H") (pin "4") (pinfunction "R12_4") (pintype "passive"))
    )
    (net (code "65") (name "/RX0_TMDS0_P") (class "Default")
      (node (ref "D15H") (pin "5") (pinfunction "IO4A_5") (pintype "bidirectional"))
      (node (ref "D15H") (pin "6") (pinfunction "IO4B_6") (pintype "bidirectional"))
      (node (ref "J11H") (pin "7") (pinfunction "7_7") (pintype "passive"))
      (node (ref "R13H") (pin "3") (pinfunction "R22_3") (pintype "passive"))
    )
    (net (code "66") (name "/RX0_TMDS1_N") (class "Default")
      (node (ref "D16H") (pin "1") (pinfunction "IO1A_1") (pintype "bidirectional"))
      (node (ref "D16H") (pin "10") (pinfunction "IO1B_10") (pintype "bidirectional"))
      (node (ref "J11H") (pin "6") (pinfunction "6_6") (pintype "passive"))
      (node (ref "R12H") (pin "2") (pinfunction "R2_2") (pintype "passive"))
    )
    (net (code "67") (name "/RX0_TMDS1_P") (class "Default")
      (node (ref "D16H") (pin "2") (pinfunction "IO2A_2") (pintype "bidirectional"))
      (node (ref "D16H") (pin "9") (pinfunction "IO2B_9") (pintype "bidirectional"))
      (node (ref "J11H") (pin "4") (pinfunction "4_4") (pintype "passive"))
      (node (ref "R12H") (pin "1") (pinfunction "R1_1") (pintype "passive"))
    )
    (net (code "68") (name "/RX0_TMDS2_N") (class "Default")
      (node (ref "D16H") (pin "4") (pinfunction "IO3A_4") (pintype "bidirectional"))
      (node (ref "D16H") (pin "7") (pinfunction "IO3B_7") (pintype "bidirectional"))
      (node (ref "J11H") (pin "3") (pinfunction "3_3") (pintype "passive"))
      (node (ref "R11H") (pin "3") (pinfunction "R22_3") (pintype "passive"))
    )
    (net (code "69") (name "/RX0_TMDS2_P") (class "Default")
      (node (ref "D16H") (pin "5") (pinfunction "IO4A_5") (pintype "bidirectional"))
      (node (ref "D16H") (pin "6") (pinfunction "IO4B_6") (pintype "bidirectional"))
      (node (ref "J11H") (pin "1") (pinfunction "1_1") (pintype "passive"))
      (node (ref "R11H") (pin "4") (pinfunction "R12_4") (pintype "passive"))
    )
    (net (code "70") (name "/RX0_TMDS3_N") (class "Default")
      (node (ref "D15H") (pin "1") (pinfunction "IO1A_1") (pintype "bidirectional"))
      (node (ref "D15H") (pin "10") (pinfunction "IO1B_10") (pintype "bidirectional"))
      (node (ref "J11H") (pin "12") (pinfunction "12_12") (pintype "passive"))
      (node (ref "R14H") (pin "2") (pinfunction "R2_2") (pintype "passive"))
    )
    (net (code "71") (name "/RX0_TMDS3_P") (class "Default")
      (node (ref "D15H") (pin "2") (pinfunction "IO2A_2") (pintype "bidirectional"))
      (node (ref "D15H") (pin "9") (pinfunction "IO2B_9") (pintype "bidirectional"))
      (node (ref "J11H") (pin "10") (pinfunction "10_10") (pintype "passive"))
      (node (ref "R14H") (pin "1") (pinfunction "R1_1") (pintype "passive"))
    )
    (net (code "72") (name "/SM_N") (class "Default")
      (node (ref "P13H") (pin "B5") (pinfunction "B5_B5") (pintype "passive"))
    )
    (net (code "73") (name "/SM_P") (class "Default")
      (node (ref "P13H") (pin "B6") (pinfunction "B6_B6") (pintype "passive"))
    )
    (net (code "74") (name "/TX0_SCL") (class "Default")
      (node (ref "P11H") (pin "3") (pinfunction "3_3") (pintype "passive"))
      (node (ref "Q20H") (pin "3") (pinfunction "D_3") (pintype "passive"))
      (node (ref "R47H") (pin "2") (pinfunction "2_2") (pintype "passive"))
    )
    (net (code "75") (name "/TX0_SCL_LV") (class "Default")
      (node (ref "Q20H") (pin "2") (pinfunction "S_2") (pintype "passive"))
      (node (ref "R48H") (pin "2") (pinfunction "2_2") (pintype "passive"))
    )
    (net (code "76") (name "/TX0_SDA") (class "Default")
      (node (ref "P14H") (pin "3") (pinfunction "3_3") (pintype "passive"))
      (node (ref "Q19H") (pin "3") (pinfunction "D_3") (pintype "passive"))
      (node (ref "R45H") (pin "2") (pinfunction "2_2") (pintype "passive"))
    )
    (net (code "77") (name "/TX0_SDA_LV") (class "Default")
      (node (ref "Q19H") (pin "2") (pinfunction "S_2") (pintype "passive"))
      (node (ref "R46H") (pin "2") (pinfunction "2_2") (pintype "passive"))
    )
    (net (code "78") (name "/TX0_TMDS0_N") (class "Default")
      (node (ref "D11H") (pin "4") (pinfunction "IO3A_4") (pintype "bidirectional"))
      (node (ref "D11H") (pin "7") (pinfunction "IO3B_7") (pintype "bidirectional"))
      (node (ref "J10H") (pin "9") (pinfunction "9_9") (pintype "passive"))
    )
    (net (code "79") (name "/TX0_TMDS0_P") (class "Default")
      (node (ref "D11H") (pin "5") (pinfunction "IO4A_5") (pintype "bidirectional"))
      (node (ref "D11H") (pin "6") (pinfunction "IO4B_6") (pintype "bidirectional"))
      (node (ref "J10H") (pin "7") (pinfunction "7_7") (pintype "passive"))
    )
    (net (code "80") (name "/TX0_TMDS1_N") (class "Default")
      (node (ref "D12H") (pin "1") (pinfunction "IO1A_1") (pintype "bidirectional"))
      (node (ref "D12H") (pin "10") (pinfunction "IO1B_10") (pintype "bidirectional"))
      (node (ref "J10H") (pin "6") (pinfunction "6_6") (pintype "passive"))
    )
    (net (code "81") (name "/TX0_TMDS1_P") (class "Default")
      (node (ref "D12H") (pin "2") (pinfunction "IO2A_2") (pintype "bidirectional"))
      (node (ref "D12H") (pin "9") (pinfunction "IO2B_9") (pintype "bidirectional"))
      (node (ref "J10H") (pin "4") (pinfunction "4_4") (pintype "passive"))
    )
    (net (code "82") (name "/TX0_TMDS2_N") (class "Default")
      (node (ref "D12H") (pin "4") (pinfunction "IO3A_4") (pintype "bidirectional"))
      (node (ref "D12H") (pin "7") (pinfunction "IO3B_7") (pintype "bidirectional"))
      (node (ref "J10H") (pin "3") (pinfunction "3_3") (pintype "passive"))
    )
    (net (code "83") (name "/TX0_TMDS2_P") (class "Default")
      (node (ref "D12H") (pin "5") (pinfunction "IO4A_5") (pintype "bidirectional"))
      (node (ref "D12H") (pin "6") (pinfunction "IO4B_6") (pintype "bidirectional"))
      (node (ref "J10H") (pin "1") (pinfunction "1_1") (pintype "passive"))
    )
    (net (code "84") (name "/TX0_TMDS3_N") (class "Default")
      (node (ref "D11H") (pin "1") (pinfunction "IO1A_1") (pintype "bidirectional"))
      (node (ref "D11H") (pin "10") (pinfunction "IO1B_10") (pintype "bidirectional"))
      (node (ref "J10H") (pin "12") (pinfunction "12_12") (pintype "passive"))
    )
    (net (code "85") (name "/TX0_TMDS3_P") (class "Default")
      (node (ref "D11H") (pin "2") (pinfunction "IO2A_2") (pintype "bidirectional"))
      (node (ref "D11H") (pin "9") (pinfunction "IO2B_9") (pintype "bidirectional"))
      (node (ref "J10H") (pin "10") (pinfunction "10_10") (pintype "passive"))
    )
    (net (code "86") (name "/TX1_CEC") (class "Default")
      (node (ref "D21H") (pin "1") (pinfunction "IO1A_1") (pintype "bidirectional"))
      (node (ref "D21H") (pin "10") (pinfunction "IO1B_10") (pintype "bidirectional"))
      (node (ref "P10H") (pin "15") (pinfunction "CEC_15") (pintype "passive"))
    )
    (net (code "87") (name "/TX1_CLK_N") (class "Default")
      (node (ref "D22H") (pin "1") (pinfunction "IO1A_1") (pintype "bidirectional"))
      (node (ref "D22H") (pin "10") (pinfunction "IO1B_10") (pintype "bidirectional"))
      (node (ref "P10H") (pin "14") (pinfunction "TMDS_CK-_14") (pintype "passive"))
    )
    (net (code "88") (name "/TX1_CLK_P") (class "Default")
      (node (ref "D22H") (pin "2") (pinfunction "IO2A_2") (pintype "bidirectional"))
      (node (ref "D22H") (pin "9") (pinfunction "IO2B_9") (pintype "bidirectional"))
      (node (ref "P10H") (pin "12") (pinfunction "TMDS_CK+_12") (pintype "passive"))
    )
    (net (code "89") (name "/TX1_HDMI_5V") (class "Default")
      (node (ref "D20H") (pin "1") (pinfunction "K_1") (pintype "passive"))
      (node (ref "F11H") (pin "2") (pinfunction "2_2") (pintype "bidirectional"))
      (node (ref "P10H") (pin "19") (pinfunction "+5V_19") (pintype "passive"))
    )
    (net (code "90") (name "/TX1_HPD") (class "Default")
      (node (ref "D21H") (pin "5") (pinfunction "IO4A_5") (pintype "bidirectional"))
      (node (ref "D21H") (pin "6") (pinfunction "IO4B_6") (pintype "bidirectional"))
      (node (ref "P10H") (pin "1") (pinfunction "HPD_1") (pintype "passive"))
      (node (ref "R40H") (pin "2") (pinfunction "2_2") (pintype "passive"))
      (node (ref "U10H") (pin "1") (pinfunction "A_1") (pintype "input"))
    )
    (net (code "91") (name "/TX1_HPD_LL") (class "Default")
      (node (ref "U10H") (pin "2") (pinfunction "~{O}_2") (pintype "output"))
    )
    (net (code "92") (name "/TX1_SCL") (class "Default")
      (node (ref "D21H") (pin "2") (pinfunction "IO2A_2") (pintype "bidirectional"))
      (node (ref "D21H") (pin "9") (pinfunction "IO2B_9") (pintype "bidirectional"))
      (node (ref "P10H") (pin "17") (pinfunction "SCL_17") (pintype "open_collector"))
      (node (ref "Q18H") (pin "3") (pinfunction "D_3") (pintype "passive"))
      (node (ref "R43H") (pin "2") (pinfunction "2_2") (pintype "passive"))
    )
    (net (code "93") (name "/TX1_SCL_LV") (class "Default")
      (node (ref "Q18H") (pin "2") (pinfunction "S_2") (pintype "passive"))
      (node (ref "R44H") (pin "2") (pinfunction "2_2") (pintype "passive"))
    )
    (net (code "94") (name "/TX1_SDA") (class "Default")
      (node (ref "D21H") (pin "4") (pinfunction "IO3A_4") (pintype "bidirectional"))
      (node (ref "D21H") (pin "7") (pinfunction "IO3B_7") (pintype "bidirectional"))
      (node (ref "P10H") (pin "18") (pinfunction "SDA_18") (pintype "open_collector"))
      (node (ref "Q17H") (pin "3") (pinfunction "D_3") (pintype "passive"))
      (node (ref "R41H") (pin "2") (pinfunction "2_2") (pintype "passive"))
    )
    (net (code "95") (name "/TX1_SDA_LV") (class "Default")
      (node (ref "Q17H") (pin "2") (pinfunction "S_2") (pintype "passive"))
      (node (ref "R42H") (pin "2") (pinfunction "2_2") (pintype "passive"))
    )
    (net (code "96") (name "/TX1_TMDS0_N") (class "Default")
      (node (ref "D22H") (pin "4") (pinfunction "IO3A_4") (pintype "bidirectional"))
      (node (ref "D22H") (pin "7") (pinfunction "IO3B_7") (pintype "bidirectional"))
      (node (ref "P10H") (pin "11") (pinfunction "TMDS0-_11") (pintype "passive"))
    )
    (net (code "97") (name "/TX1_TMDS0_P") (class "Default")
      (node (ref "D22H") (pin "5") (pinfunction "IO4A_5") (pintype "bidirectional"))
      (node (ref "D22H") (pin "6") (pinfunction "IO4B_6") (pintype "bidirectional"))
      (node (ref "P10H") (pin "9") (pinfunction "TMDS0+_9") (pintype "passive"))
    )
    (net (code "98") (name "/TX1_TMDS1_N") (class "Default")
      (node (ref "D23H") (pin "1") (pinfunction "IO1A_1") (pintype "bidirectional"))
      (node (ref "D23H") (pin "10") (pinfunction "IO1B_10") (pintype "bidirectional"))
      (node (ref "P10H") (pin "8") (pinfunction "TMDS1-_8") (pintype "passive"))
    )
    (net (code "99") (name "/TX1_TMDS1_P") (class "Default")
      (node (ref "D23H") (pin "2") (pinfunction "IO2A_2") (pintype "bidirectional"))
      (node (ref "D23H") (pin "9") (pinfunction "IO2B_9") (pintype "bidirectional"))
      (node (ref "P10H") (pin "6") (pinfunction "TMDS1+_6") (pintype "passive"))
    )
    (net (code "100") (name "/TX1_TMDS2_N") (class "Default")
      (node (ref "D23H") (pin "4") (pinfunction "IO3A_4") (pintype "bidirectional"))
      (node (ref "D23H") (pin "7") (pinfunction "IO3B_7") (pintype "bidirectional"))
      (node (ref "P10H") (pin "5") (pinfunction "TMDS2-_5") (pintype "passive"))
    )
    (net (code "101") (name "/TX1_TMDS2_P") (class "Default")
      (node (ref "D23H") (pin "5") (pinfunction "IO4A_5") (pintype "bidirectional"))
      (node (ref "D23H") (pin "6") (pinfunction "IO4B_6") (pintype "bidirectional"))
      (node (ref "P10H") (pin "3") (pinfunction "TMDS2+_3") (pintype "passive"))
    )
    (net (code "102") (name "/TX_HDMI_5V") (class "Default")
      (node (ref "D13H") (pin "1") (pinfunction "K_1") (pintype "passive"))
      (node (ref "F10H") (pin "2") (pinfunction "2_2") (pintype "bidirectional"))
      (node (ref "J10H") (pin "18") (pinfunction "18_18") (pintype "passive"))
      (node (ref "Q13H") (pin "2") (pinfunction "S_2") (pintype "passive"))
      (node (ref "R27H") (pin "1") (pinfunction "1_1") (pintype "passive"))
      (node (ref "R49H") (pin "1") (pinfunction "1_1") (pintype "passive"))
      (node (ref "R50H") (pin "1") (pinfunction "1_1") (pintype "passive"))
    )
    (net (code "103") (name "/WAKE#") (class "Default")
      (node (ref "P13H") (pin "B11") (pinfunction "B11_B11") (pintype "passive"))
    )
    (net (code "104") (name "GND") (class "Default")
      (node (ref "C10H") (pin "2") (pinfunction "2_2") (pintype "passive"))
      (node (ref "C12H") (pin "2") (pinfunction "2_2") (pintype "passive"))
      (node (ref "D10H") (pin "3") (pinfunction "GND1_3") (pintype "input"))
      (node (ref "D11H") (pin "3") (pinfunction "GND1_3") (pintype "input"))
      (node (ref "D12H") (pin "3") (pinfunction "GND1_3") (pintype "input"))
      (node (ref "D13H") (pin "2") (pinfunction "A_2") (pintype "passive"))
      (node (ref "D14H") (pin "3") (pinfunction "GND1_3") (pintype "input"))
      (node (ref "D15H") (pin "3") (pinfunction "GND1_3") (pintype "input"))
      (node (ref "D16H") (pin "3") (pinfunction "GND1_3") (pintype "input"))
      (node (ref "D17H") (pin "3") (pinfunction "GND1_3") (pintype "input"))
      (node (ref "D18H") (pin "3") (pinfunction "GND1_3") (pintype "input"))
      (node (ref "D19H") (pin "3") (pinfunction "GND1_3") (pintype "input"))
      (node (ref "D20H") (pin "2") (pinfunction "A_2") (pintype "passive"))
      (node (ref "D21H") (pin "3") (pinfunction "GND1_3") (pintype "input"))
      (node (ref "D22H") (pin "3") (pinfunction "GND1_3") (pintype "input"))
      (node (ref "D23H") (pin "3") (pinfunction "GND1_3") (pintype "input"))
      (node (ref "J10H") (pin "0") (pinfunction "GND_0") (pintype "passive"))
      (node (ref "J10H") (pin "11") (pinfunction "11_11") (pintype "passive"))
      (node (ref "J10H") (pin "17") (pinfunction "17_17") (pintype "passive"))
      (node (ref "J10H") (pin "2") (pinfunction "2_2") (pintype "passive"))
      (node (ref "J10H") (pin "5") (pinfunction "5_5") (pintype "passive"))
      (node (ref "J10H") (pin "8") (pinfunction "8_8") (pintype "passive"))
      (node (ref "J11H") (pin "0") (pinfunction "GND_0") (pintype "passive"))
      (node (ref "J11H") (pin "11") (pinfunction "11_11") (pintype "passive"))
      (node (ref "J11H") (pin "17") (pinfunction "17_17") (pintype "passive"))
      (node (ref "J11H") (pin "2") (pinfunction "2_2") (pintype "passive"))
      (node (ref "J11H") (pin "5") (pinfunction "5_5") (pintype "passive"))
      (node (ref "J11H") (pin "8") (pinfunction "8_8") (pintype "passive"))
      (node (ref "J12H") (pin "0") (pinfunction "GND_0") (pintype "passive"))
      (node (ref "J12H") (pin "11") (pinfunction "11_11") (pintype "passive"))
      (node (ref "J12H") (pin "17") (pinfunction "17_17") (pintype "passive"))
      (node (ref "J12H") (pin "2") (pinfunction "2_2") (pintype "passive"))
      (node (ref "J12H") (pin "5") (pinfunction "5_5") (pintype "passive"))
      (node (ref "J12H") (pin "8") (pinfunction "8_8") (pintype "passive"))
      (node (ref "P10H") (pin "0") (pinfunction "SHELL_0") (pintype "passive"))
      (node (ref "P10H") (pin "10") (pinfunction "Shield_10") (pintype "power_in"))
      (node (ref "P10H") (pin "13") (pinfunction "Shield_13") (pintype "power_in"))
      (node (ref "P10H") (pin "16") (pinfunction "GND_16") (pintype "power_in"))
      (node (ref "P10H") (pin "4") (pinfunction "Shield_4") (pintype "power_in"))
      (node (ref "P10H") (pin "7") (pinfunction "Shield_7") (pintype "power_in"))
      (node (ref "P13H") (pin "A12") (pinfunction "A12_A12") (pintype "passive"))
      (node (ref "P13H") (pin "A15") (pinfunction "A15_A15") (pintype "passive"))
      (node (ref "P13H") (pin "A18") (pinfunction "A18_A18") (pintype "passive"))
      (node (ref "P13H") (pin "A20") (pinfunction "A20_A20") (pintype "passive"))
      (node (ref "P13H") (pin "A23") (pinfunction "A23_A23") (pintype "passive"))
      (node (ref "P13H") (pin "A24") (pinfunction "A24_A24") (pintype "passive"))
      (node (ref "P13H") (pin "A27") (pinfunction "A27_A27") (pintype "passive"))
      (node (ref "P13H") (pin "A28") (pinfunction "A28_A28") (pintype "passive"))
      (node (ref "P13H") (pin "A31") (pinfunction "A31_A31") (pintype "passive"))
      (node (ref "P13H") (pin "A4") (pinfunction "A4_A4") (pintype "passive"))
      (node (ref "P13H") (pin "B13") (pinfunction "B13_B13") (pintype "passive"))
      (node (ref "P13H") (pin "B16") (pinfunction "B16_B16") (pintype "passive"))
      (node (ref "P13H") (pin "B18") (pinfunction "B18_B18") (pintype "passive"))
      (node (ref "P13H") (pin "B21") (pinfunction "B21_B21") (pintype "passive"))
      (node (ref "P13H") (pin "B22") (pinfunction "B22_B22") (pintype "passive"))
      (node (ref "P13H") (pin "B25") (pinfunction "B25_B25") (pintype "passive"))
      (node (ref "P13H") (pin "B26") (pinfunction "B26_B26") (pintype "passive"))
      (node (ref "P13H") (pin "B29") (pinfunction "B29_B29") (pintype "passive"))
      (node (ref "P13H") (pin "B32") (pinfunction "B32_B32") (pintype "passive"))
      (node (ref "P13H") (pin "B4") (pinfunction "B4_B4") (pintype "passive"))
      (node (ref "P13H") (pin "B7") (pinfunction "B7_B7") (pintype "passive"))
      (node (ref "P15H") (pin "1") (pinfunction "1_1") (pintype "passive"))
      (node (ref "Q11H") (pin "2") (pinfunction "S_2") (pintype "passive"))
      (node (ref "Q12H") (pin "2") (pinfunction "S_2") (pintype "passive"))
      (node (ref "Q14H") (pin "2") (pinfunction "S_2") (pintype "passive"))
      (node (ref "Q15H") (pin "2") (pinfunction "S_2") (pintype "passive"))
      (node (ref "R10H") (pin "1") (pinfunction "1_1") (pintype "passive"))
      (node (ref "R17H") (pin "2") (pinfunction "2_2") (pintype "passive"))
      (node (ref "R20H") (pin "2") (pinfunction "2_2") (pintype "passive"))
      (node (ref "R31H") (pin "2") (pinfunction "2_2") (pintype "passive"))
      (node (ref "R33H") (pin "2") (pinfunction "2_2") (pintype "passive"))
      (node (ref "R34H") (pin "2") (pinfunction "2_2") (pintype "passive"))
      (node (ref "R40H") (pin "1") (pinfunction "1_1") (pintype "passive"))
      (node (ref "U10H") (pin "7") (pinfunction "GND_7") (pintype "power_in"))
    )
    (net (code "105") (name "Net-(Q10H-G)") (class "Default")
      (node (ref "Q10H") (pin "1") (pinfunction "G_1") (pintype "passive"))
      (node (ref "Q11H") (pin "3") (pinfunction "D_3") (pintype "passive"))
      (node (ref "R16H") (pin "2") (pinfunction "2_2") (pintype "passive"))
    )
    (net (code "106") (name "Net-(Q12H-D)") (class "Default")
      (node (ref "Q12H") (pin "3") (pinfunction "D_3") (pintype "passive"))
      (node (ref "R18H") (pin "1") (pinfunction "1_1") (pintype "passive"))
    )
    (net (code "107") (name "Net-(Q13H-D)") (class "Default")
      (node (ref "Q13H") (pin "3") (pinfunction "D_3") (pintype "passive"))
      (node (ref "R32H") (pin "2") (pinfunction "2_2") (pintype "passive"))
    )
    (net (code "108") (name "Net-(Q13H-G)") (class "Default")
      (node (ref "Q13H") (pin "1") (pinfunction "G_1") (pintype "passive"))
      (node (ref "Q14H") (pin "3") (pinfunction "D_3") (pintype "passive"))
      (node (ref "R27H") (pin "2") (pinfunction "2_2") (pintype "passive"))
    )
    (net (code "109") (name "P3.3V") (class "Default")
      (node (ref "C10H") (pin "1") (pinfunction "1_1") (pintype "passive"))
      (node (ref "C12H") (pin "1") (pinfunction "1_1") (pintype "passive"))
      (node (ref "Q16H") (pin "1") (pinfunction "G_1") (pintype "passive"))
      (node (ref "Q17H") (pin "1") (pinfunction "G_1") (pintype "passive"))
      (node (ref "Q18H") (pin "1") (pinfunction "G_1") (pintype "passive"))
      (node (ref "Q19H") (pin "1") (pinfunction "G_1") (pintype "passive"))
      (node (ref "Q20H") (pin "1") (pinfunction "G_1") (pintype "passive"))
      (node (ref "R11H") (pin "1") (pinfunction "R1_1") (pintype "passive"))
      (node (ref "R11H") (pin "2") (pinfunction "R2_2") (pintype "passive"))
      (node (ref "R12H") (pin "3") (pinfunction "R22_3") (pintype "passive"))
      (node (ref "R12H") (pin "4") (pinfunction "R12_4") (pintype "passive"))
      (node (ref "R13H") (pin "1") (pinfunction "R1_1") (pintype "passive"))
      (node (ref "R13H") (pin "2") (pinfunction "R2_2") (pintype "passive"))
      (node (ref "R14H") (pin "3") (pinfunction "R22_3") (pintype "passive"))
      (node (ref "R14H") (pin "4") (pinfunction "R12_4") (pintype "passive"))
      (node (ref "R19H") (pin "3") (pinfunction "R22_3") (pintype "passive"))
      (node (ref "R19H") (pin "4") (pinfunction "R12_4") (pintype "passive"))
      (node (ref "R21H") (pin "1") (pinfunction "R1_1") (pintype "passive"))
      (node (ref "R21H") (pin "2") (pinfunction "R2_2") (pintype "passive"))
      (node (ref "R22H") (pin "1") (pinfunction "R1_1") (pintype "passive"))
      (node (ref "R22H") (pin "2") (pinfunction "R2_2") (pintype "passive"))
      (node (ref "R25H") (pin "3") (pinfunction "R22_3") (pintype "passive"))
      (node (ref "R25H") (pin "4") (pinfunction "R12_4") (pintype "passive"))
      (node (ref "R36H") (pin "1") (pinfunction "1_1") (pintype "passive"))
      (node (ref "R42H") (pin "1") (pinfunction "1_1") (pintype "passive"))
      (node (ref "R44H") (pin "1") (pinfunction "1_1") (pintype "passive"))
      (node (ref "R46H") (pin "1") (pinfunction "1_1") (pintype "passive"))
      (node (ref "R48H") (pin "1") (pinfunction "1_1") (pintype "passive"))
      (node (ref "U10H") (pin "14") (pinfunction "VCC_14") (pintype "power_in"))
    )
    (net (code "110") (name "P5.0V") (class "Default")
      (node (ref "F10H") (pin "1") (pinfunction "1_1") (pintype "bidirectional"))
      (node (ref "F11H") (pin "1") (pinfunction "1_1") (pintype "bidirectional"))
      (node (ref "Q10H") (pin "2") (pinfunction "S_2") (pintype "passive"))
      (node (ref "R16H") (pin "1") (pinfunction "1_1") (pintype "passive"))
      (node (ref "R41H") (pin "1") (pinfunction "1_1") (pintype "passive"))
      (node (ref "R43H") (pin "1") (pinfunction "1_1") (pintype "passive"))
      (node (ref "R45H") (pin "1") (pinfunction "1_1") (pintype "passive"))
      (node (ref "R47H") (pin "1") (pinfunction "1_1") (pintype "passive"))
    )
    (net (code "111") (name "P12V") (class "Default")
      (node (ref "P13H") (pin "A2") (pinfunction "A2_A2") (pintype "passive"))
      (node (ref "P13H") (pin "A3") (pinfunction "A3_A3") (pintype "passive"))
      (node (ref "P13H") (pin "B1") (pinfunction "B1_B1") (pintype "passive"))
      (node (ref "P13H") (pin "B2") (pinfunction "B2_B2") (pintype "passive"))
      (node (ref "P13H") (pin "B3") (pinfunction "B3_B3") (pintype "passive"))
    )
    (net (code "112") (name "unconnected-(J10H-Pad14)") (class "Default")
      (node (ref "J10H") (pin "14") (pinfunction "14_14") (pintype "passive"))
    )
    (net (code "113") (name "unconnected-(J11H-Pad14)") (class "Default")
      (node (ref "J11H") (pin "14") (pinfunction "14_14") (pintype "passive"))
    )
    (net (code "114") (name "unconnected-(J11H-Pad18)") (class "Default")
      (node (ref "J11H") (pin "18") (pinfunction "18_18") (pintype "passive"))
    )
    (net (code "115") (name "unconnected-(J12H-Pad14)") (class "Default")
      (node (ref "J12H") (pin "14") (pinfunction "14_14") (pintype "passive"))
    )
    (net (code "116") (name "unconnected-(P10H-Utility-Pad2)") (class "Default")
      (node (ref "P10H") (pin "2") (pinfunction "Utility_2") (pintype "passive+no_connect"))
    )
    (net (code "117") (name "unconnected-(P13H-PadA19)") (class "Default")
      (node (ref "P13H") (pin "A19") (pinfunction "A19_A19") (pintype "passive+no_connect"))
    )
    (net (code "118") (name "unconnected-(P13H-PadA32)") (class "Default")
      (node (ref "P13H") (pin "A32") (pinfunction "A32_A32") (pintype "passive"))
    )
    (net (code "119") (name "unconnected-(P13H-PadB30)") (class "Default")
      (node (ref "P13H") (pin "B30") (pinfunction "B30_B30") (pintype "passive"))
    )
  )
)
